# OSCILLATEUR.net
KiCad netlist of a schematic drawn in Altium Designer
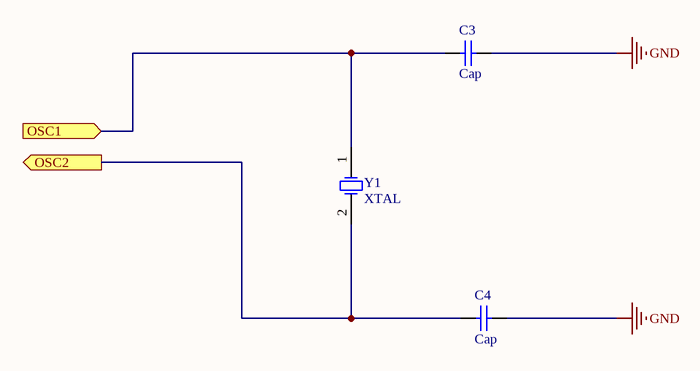
[diagram p0: OSCILLATEUR.SchDoc]

(export (version "E")
  (design (tool "Eeschema 10.0.6"))
  (components
    (comp (ref "C3")
      (value "Cap")
      (footprint "RAD-0.3")
      (description "Capacitor")
      (fields (field (name "PUBLISHER") "Altium Limited"))
      (libsource (lib "Miscellaneous Devices") (part "Cap"))
    )
    (comp (ref "C4")
      (value "Cap")
      (footprint "RAD-0.3")
      (description "Capacitor")
      (fields (field (name "PUBLISHER") "Altium Limited"))
      (libsource (lib "Miscellaneous Devices") (part "Cap"))
    )
    (comp (ref "Y1")
      (value "XTAL")
      (footprint "R38")
      (description "Crystal Oscillator")
      (fields (field (name "PUBLISHER") "Altium Limited"))
      (libsource (lib "Miscellaneous Devices") (part "XTAL"))
    )
  )
  (nets
    (net (code "1") (name "/OSC1") (class "Default")
      (node (ref "C3") (pin "1") (pinfunction "1_1") (pintype "passive"))
      (node (ref "Y1") (pin "1") (pinfunction "OSC1_1") (pintype "passive"))
    )
    (net (code "2") (name "/OSC2") (class "Default")
      (node (ref "C4") (pin "1") (pinfunction "1_1") (pintype "passive"))
      (node (ref "Y1") (pin "2") (pinfunction "OSC2_2") (pintype "passive"))
    )
    (net (code "3") (name "GND") (class "Default")
      (node (ref "C3") (pin "2") (pinfunction "2_2") (pintype "passive"))
      (node (ref "C4") (pin "2") (pinfunction "2_2") (pintype "passive"))
    )
  )
)
